# RC_module.net
KiCad netlist of a schematic drawn in EAGLE
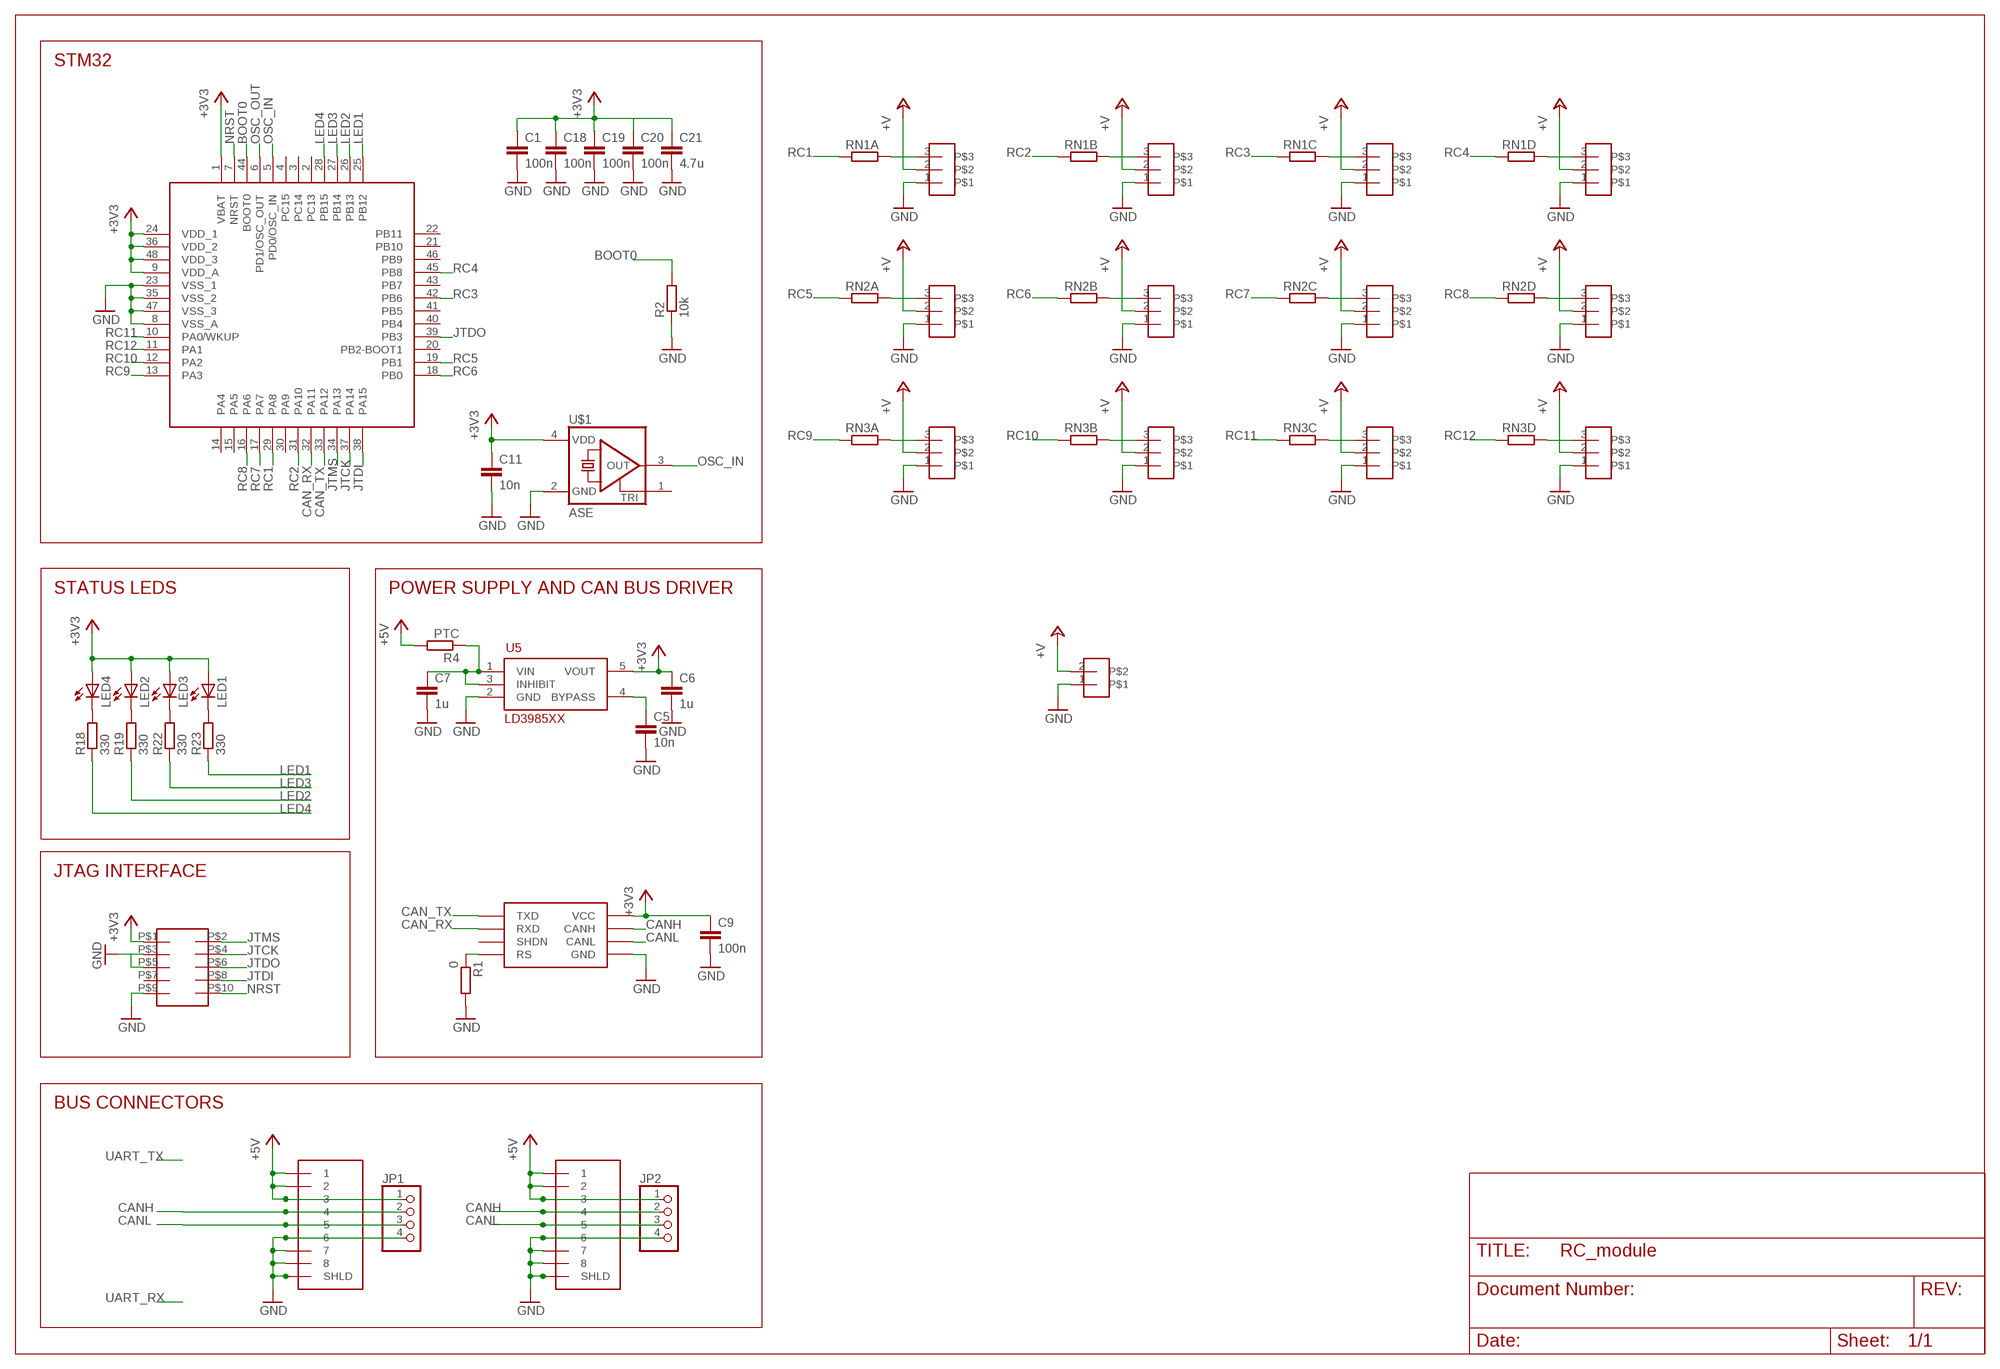
[diagram p0: schematic, sheet 1]

(export (version "E")
  (design (tool "Eeschema 10.0.6"))
  (components
    (comp (ref "1")
      (value "RJ45-43860")
      (footprint "eagle-import:0438600010")
      (libsource (lib "eagle-import") (part "RJ45-43860"))
    )
    (comp (ref "2")
      (value "RJ45-43860")
      (footprint "eagle-import:0438600010")
      (libsource (lib "eagle-import") (part "RJ45-43860"))
    )
    (comp (ref "C1")
      (value "100n")
      (footprint "eagle-import:C0603")
      (libsource (lib "eagle-import") (part "C-EUC0603"))
    )
    (comp (ref "C5")
      (value "10n")
      (footprint "eagle-import:C0603")
      (libsource (lib "eagle-import") (part "C-EUC0603"))
    )
    (comp (ref "C6")
      (value "1u")
      (footprint "eagle-import:C0603")
      (libsource (lib "eagle-import") (part "C-EUC0603"))
    )
    (comp (ref "C7")
      (value "1u")
      (footprint "eagle-import:C0603")
      (libsource (lib "eagle-import") (part "C-EUC0603"))
    )
    (comp (ref "C9")
      (value "100n")
      (footprint "eagle-import:C0603")
      (libsource (lib "eagle-import") (part "C-EUC0603"))
    )
    (comp (ref "C11")
      (value "10n")
      (footprint "eagle-import:C0603")
      (libsource (lib "eagle-import") (part "C-EUC0603"))
    )
    (comp (ref "C18")
      (value "100n")
      (footprint "eagle-import:C0603")
      (libsource (lib "eagle-import") (part "C-EUC0603"))
    )
    (comp (ref "C19")
      (value "100n")
      (footprint "eagle-import:C0603")
      (libsource (lib "eagle-import") (part "C-EUC0603"))
    )
    (comp (ref "C20")
      (value "100n")
      (footprint "eagle-import:C0603")
      (libsource (lib "eagle-import") (part "C-EUC0603"))
    )
    (comp (ref "C21")
      (value "4.7u")
      (footprint "eagle-import:C0805")
      (libsource (lib "eagle-import") (part "C-EUC0805"))
    )
    (comp (ref "JP1")
      (value "PINHD-1X4")
      (footprint "eagle-import:1X04")
      (libsource (lib "eagle-import") (part "PINHD-1X4"))
    )
    (comp (ref "JP2")
      (value "PINHD-1X4")
      (footprint "eagle-import:1X04")
      (libsource (lib "eagle-import") (part "PINHD-1X4"))
    )
    (comp (ref "LED1")
      (value "LEDCHIPLED_0805")
      (footprint "eagle-import:CHIPLED_0805")
      (libsource (lib "eagle-import") (part "LEDCHIPLED_0805"))
    )
    (comp (ref "LED2")
      (value "LEDCHIPLED_0805")
      (footprint "eagle-import:CHIPLED_0805")
      (libsource (lib "eagle-import") (part "LEDCHIPLED_0805"))
    )
    (comp (ref "LED3")
      (value "LEDCHIPLED_0805")
      (footprint "eagle-import:CHIPLED_0805")
      (libsource (lib "eagle-import") (part "LEDCHIPLED_0805"))
    )
    (comp (ref "LED4")
      (value "LEDCHIPLED_0805")
      (footprint "eagle-import:CHIPLED_0805")
      (libsource (lib "eagle-import") (part "LEDCHIPLED_0805"))
    )
    (comp (ref "R1")
      (value "0")
      (footprint "eagle-import:R0603")
      (libsource (lib "eagle-import") (part "R-EU_R0603"))
    )
    (comp (ref "R2")
      (value "10k")
      (footprint "eagle-import:R0603")
      (libsource (lib "eagle-import") (part "R-EU_R0603"))
    )
    (comp (ref "R4")
      (value "PTC")
      (footprint "eagle-import:R0603")
      (libsource (lib "eagle-import") (part "R-EU_R0603"))
    )
    (comp (ref "R18")
      (value "330")
      (footprint "eagle-import:R0603")
      (libsource (lib "eagle-import") (part "R-EU_R0603"))
    )
    (comp (ref "R19")
      (value "330")
      (footprint "eagle-import:R0603")
      (libsource (lib "eagle-import") (part "R-EU_R0603"))
    )
    (comp (ref "R22")
      (value "330")
      (footprint "eagle-import:R0603")
      (libsource (lib "eagle-import") (part "R-EU_R0603"))
    )
    (comp (ref "R23")
      (value "330")
      (footprint "eagle-import:R0603")
      (libsource (lib "eagle-import") (part "R-EU_R0603"))
    )
    (comp (ref "RN1")
      (value "RESISTOR_ARRAY_4")
      (footprint "eagle-import:RN8P-4R-CRA06S")
      (libsource (lib "eagle-import") (part "RESISTOR_ARRAY_4"))
    )
    (comp (ref "RN2")
      (value "RESISTOR_ARRAY_4")
      (footprint "eagle-import:RN8P-4R-CRA06S")
      (libsource (lib "eagle-import") (part "RESISTOR_ARRAY_4"))
    )
    (comp (ref "RN3")
      (value "RESISTOR_ARRAY_4")
      (footprint "eagle-import:RN8P-4R-CRA06S")
      (libsource (lib "eagle-import") (part "RESISTOR_ARRAY_4"))
    )
    (comp (ref "SOT1")
      (value "MAX3051")
      (footprint "eagle-import:SOT23-8L")
      (libsource (lib "eagle-import") (part "MAX3051"))
    )
    (comp (ref "U$1")
      (value "ASE")
      (footprint "eagle-import:ASE")
      (libsource (lib "eagle-import") (part "ASE"))
    )
    (comp (ref "U$2")
      (value "PINHD-3")
      (footprint "eagle-import:1X03")
      (libsource (lib "eagle-import") (part "PINHD-3"))
    )
    (comp (ref "U$3")
      (value "PINHD-3")
      (footprint "eagle-import:1X03")
      (libsource (lib "eagle-import") (part "PINHD-3"))
    )
    (comp (ref "U$4")
      (value "FTSH-105")
      (footprint "eagle-import:FTSH-105")
      (libsource (lib "eagle-import") (part "FTSH-105"))
    )
    (comp (ref "U$5")
      (value "PINHD-3")
      (footprint "eagle-import:1X03")
      (libsource (lib "eagle-import") (part "PINHD-3"))
    )
    (comp (ref "U$6")
      (value "PINHD-3")
      (footprint "eagle-import:1X03")
      (libsource (lib "eagle-import") (part "PINHD-3"))
    )
    (comp (ref "U$7")
      (value "PINHD-3")
      (footprint "eagle-import:1X03")
      (libsource (lib "eagle-import") (part "PINHD-3"))
    )
    (comp (ref "U$8")
      (value "PINHD-3")
      (footprint "eagle-import:1X03")
      (libsource (lib "eagle-import") (part "PINHD-3"))
    )
    (comp (ref "U$9")
      (value "PINHD-3")
      (footprint "eagle-import:1X03")
      (libsource (lib "eagle-import") (part "PINHD-3"))
    )
    (comp (ref "U$10")
      (value "PINHD-3")
      (footprint "eagle-import:1X03")
      (libsource (lib "eagle-import") (part "PINHD-3"))
    )
    (comp (ref "U$11")
      (value "PINHD-3")
      (footprint "eagle-import:1X03")
      (libsource (lib "eagle-import") (part "PINHD-3"))
    )
    (comp (ref "U$12")
      (value "PINHD-3")
      (footprint "eagle-import:1X03")
      (libsource (lib "eagle-import") (part "PINHD-3"))
    )
    (comp (ref "U$13")
      (value "PINHD-3")
      (footprint "eagle-import:1X03")
      (libsource (lib "eagle-import") (part "PINHD-3"))
    )
    (comp (ref "U$14")
      (value "PINHD-3")
      (footprint "eagle-import:1X03")
      (libsource (lib "eagle-import") (part "PINHD-3"))
    )
    (comp (ref "U$15")
      (value "SCREWTERMINAL_3-3")
      (footprint "eagle-import:SCREWTERMINAL-3.5MM-2")
      (libsource (lib "eagle-import") (part "SCREWTERMINAL_3-3"))
    )
    (comp (ref "U1")
      (value "STM32F103CX")
      (footprint "eagle-import:LQFP48")
      (libsource (lib "eagle-import") (part "STM32F103CX"))
    )
    (comp (ref "U5")
      (value "LD3985XX")
      (footprint "eagle-import:SOT23-5L")
      (libsource (lib "eagle-import") (part "LD3985XX"))
    )
  )
  (nets
    (net (code "1") (name "+3V3") (class "Default")
      (node (ref "C1") (pin "1") (pinfunction "1_1") (pintype "passive"))
      (node (ref "C11") (pin "1") (pinfunction "1_1") (pintype "passive"))
      (node (ref "C18") (pin "1") (pinfunction "1_1") (pintype "passive"))
      (node (ref "C19") (pin "1") (pinfunction "1_1") (pintype "passive"))
      (node (ref "C20") (pin "1") (pinfunction "1_1") (pintype "passive"))
      (node (ref "C21") (pin "1") (pinfunction "1_1") (pintype "passive"))
      (node (ref "C6") (pin "1") (pinfunction "1_1") (pintype "passive"))
      (node (ref "C9") (pin "1") (pinfunction "1_1") (pintype "passive"))
      (node (ref "LED1") (pin "A") (pinfunction "A_A") (pintype "passive"))
      (node (ref "LED2") (pin "A") (pinfunction "A_A") (pintype "passive"))
      (node (ref "LED3") (pin "A") (pinfunction "A_A") (pintype "passive"))
      (node (ref "LED4") (pin "A") (pinfunction "A_A") (pintype "passive"))
      (node (ref "SOT1") (pin "P$3") (pinfunction "VCC_P$3") (pintype "bidirectional"))
      (node (ref "U$1") (pin "4") (pinfunction "VDD_4") (pintype "power_in"))
      (node (ref "U$4") (pin "P$1") (pinfunction "P$1_P$1") (pintype "bidirectional"))
      (node (ref "U1") (pin "1") (pinfunction "VBAT_1") (pintype "bidirectional"))
      (node (ref "U1") (pin "24") (pinfunction "VDD_1_24") (pintype "bidirectional"))
      (node (ref "U1") (pin "36") (pinfunction "VDD_2_36") (pintype "bidirectional"))
      (node (ref "U1") (pin "48") (pinfunction "VDD_3_48") (pintype "bidirectional"))
      (node (ref "U1") (pin "9") (pinfunction "VDD_A_9") (pintype "bidirectional"))
      (node (ref "U5") (pin "5") (pinfunction "VOUT_5") (pintype "bidirectional"))
    )
    (net (code "2") (name "+5V") (class "Default")
      (node (ref "1") (pin "P$1") (pinfunction "1_P$1") (pintype "bidirectional"))
      (node (ref "1") (pin "P$2") (pinfunction "2_P$2") (pintype "bidirectional"))
      (node (ref "1") (pin "P$3") (pinfunction "3_P$3") (pintype "bidirectional"))
      (node (ref "2") (pin "P$1") (pinfunction "1_P$1") (pintype "bidirectional"))
      (node (ref "2") (pin "P$2") (pinfunction "2_P$2") (pintype "bidirectional"))
      (node (ref "2") (pin "P$3") (pinfunction "3_P$3") (pintype "bidirectional"))
      (node (ref "JP1") (pin "1") (pinfunction "1_1") (pintype "passive"))
      (node (ref "JP2") (pin "1") (pinfunction "1_1") (pintype "passive"))
      (node (ref "R4") (pin "2") (pinfunction "2_2") (pintype "passive"))
    )
    (net (code "3") (name "+V") (class "Default")
      (node (ref "U$10") (pin "2") (pinfunction "P$2_2") (pintype "bidirectional"))
      (node (ref "U$11") (pin "2") (pinfunction "P$2_2") (pintype "bidirectional"))
      (node (ref "U$12") (pin "2") (pinfunction "P$2_2") (pintype "bidirectional"))
      (node (ref "U$13") (pin "2") (pinfunction "P$2_2") (pintype "bidirectional"))
      (node (ref "U$14") (pin "2") (pinfunction "P$2_2") (pintype "bidirectional"))
      (node (ref "U$15") (pin "2") (pinfunction "P$2_2") (pintype "bidirectional"))
      (node (ref "U$2") (pin "2") (pinfunction "P$2_2") (pintype "bidirectional"))
      (node (ref "U$3") (pin "2") (pinfunction "P$2_2") (pintype "bidirectional"))
      (node (ref "U$5") (pin "2") (pinfunction "P$2_2") (pintype "bidirectional"))
      (node (ref "U$6") (pin "2") (pinfunction "P$2_2") (pintype "bidirectional"))
      (node (ref "U$7") (pin "2") (pinfunction "P$2_2") (pintype "bidirectional"))
      (node (ref "U$8") (pin "2") (pinfunction "P$2_2") (pintype "bidirectional"))
      (node (ref "U$9") (pin "2") (pinfunction "P$2_2") (pintype "bidirectional"))
    )
    (net (code "4") (name "/BOOT0") (class "Default")
      (node (ref "R2") (pin "2") (pinfunction "2_2") (pintype "passive"))
      (node (ref "U1") (pin "44") (pinfunction "BOOT0_44") (pintype "bidirectional"))
    )
    (net (code "5") (name "/CANH") (class "Default")
      (node (ref "1") (pin "P$4") (pinfunction "4_P$4") (pintype "bidirectional"))
      (node (ref "2") (pin "P$4") (pinfunction "4_P$4") (pintype "bidirectional"))
      (node (ref "JP1") (pin "2") (pinfunction "2_2") (pintype "passive"))
      (node (ref "JP2") (pin "2") (pinfunction "2_2") (pintype "passive"))
      (node (ref "SOT1") (pin "P$7") (pinfunction "CANH_P$7") (pintype "bidirectional"))
    )
    (net (code "6") (name "/CANL") (class "Default")
      (node (ref "1") (pin "P$5") (pinfunction "5_P$5") (pintype "bidirectional"))
      (node (ref "2") (pin "P$5") (pinfunction "5_P$5") (pintype "bidirectional"))
      (node (ref "JP1") (pin "3") (pinfunction "3_3") (pintype "passive"))
      (node (ref "JP2") (pin "3") (pinfunction "3_3") (pintype "passive"))
      (node (ref "SOT1") (pin "P$6") (pinfunction "CANL_P$6") (pintype "bidirectional"))
    )
    (net (code "7") (name "/CAN_RX") (class "Default")
      (node (ref "SOT1") (pin "P$4") (pinfunction "RXD_P$4") (pintype "bidirectional"))
      (node (ref "U1") (pin "32") (pinfunction "PA11_32") (pintype "bidirectional"))
    )
    (net (code "8") (name "/CAN_TX") (class "Default")
      (node (ref "SOT1") (pin "P$1") (pinfunction "TXD_P$1") (pintype "bidirectional"))
      (node (ref "U1") (pin "33") (pinfunction "PA12_33") (pintype "bidirectional"))
    )
    (net (code "9") (name "/JTCK") (class "Default")
      (node (ref "U$4") (pin "P$4") (pinfunction "P$4_P$4") (pintype "bidirectional"))
      (node (ref "U1") (pin "37") (pinfunction "PA14_37") (pintype "bidirectional"))
    )
    (net (code "10") (name "/JTDI") (class "Default")
      (node (ref "U$4") (pin "P$8") (pinfunction "P$8_P$8") (pintype "bidirectional"))
      (node (ref "U1") (pin "38") (pinfunction "PA15_38") (pintype "bidirectional"))
    )
    (net (code "11") (name "/JTDO") (class "Default")
      (node (ref "U$4") (pin "P$6") (pinfunction "P$6_P$6") (pintype "bidirectional"))
      (node (ref "U1") (pin "39") (pinfunction "PB3_39") (pintype "bidirectional"))
    )
    (net (code "12") (name "/JTMS") (class "Default")
      (node (ref "U$4") (pin "P$2") (pinfunction "P$2_P$2") (pintype "bidirectional"))
      (node (ref "U1") (pin "34") (pinfunction "PA13_34") (pintype "bidirectional"))
    )
    (net (code "13") (name "/LED1") (class "Default")
      (node (ref "R23") (pin "1") (pinfunction "1_1") (pintype "passive"))
      (node (ref "U1") (pin "25") (pinfunction "PB12_25") (pintype "bidirectional"))
    )
    (net (code "14") (name "/LED2") (class "Default")
      (node (ref "R19") (pin "1") (pinfunction "1_1") (pintype "passive"))
      (node (ref "U1") (pin "26") (pinfunction "PB13_26") (pintype "bidirectional"))
    )
    (net (code "15") (name "/LED3") (class "Default")
      (node (ref "R22") (pin "1") (pinfunction "1_1") (pintype "passive"))
      (node (ref "U1") (pin "27") (pinfunction "PB14_27") (pintype "bidirectional"))
    )
    (net (code "16") (name "/LED4") (class "Default")
      (node (ref "R18") (pin "1") (pinfunction "1_1") (pintype "passive"))
      (node (ref "U1") (pin "28") (pinfunction "PB15_28") (pintype "bidirectional"))
    )
    (net (code "17") (name "/NRST") (class "Default")
      (node (ref "U$4") (pin "P$10") (pinfunction "P$10_P$10") (pintype "bidirectional"))
      (node (ref "U1") (pin "7") (pinfunction "NRST_7") (pintype "bidirectional"))
    )
    (net (code "18") (name "/OSC_IN") (class "Default")
      (node (ref "U$1") (pin "3") (pinfunction "OUT_3") (pintype "output"))
      (node (ref "U1") (pin "5") (pinfunction "PD0/OSC_IN_5") (pintype "bidirectional"))
    )
    (net (code "19") (name "/OSC_OUT") (class "Default")
      (node (ref "U1") (pin "6") (pinfunction "PD1/OSC_OUT_6") (pintype "bidirectional"))
    )
    (net (code "20") (name "/RC1") (class "Default")
      (node (ref "RN1") (pin "1") (pinfunction "1_1") (pintype "passive"))
      (node (ref "U1") (pin "29") (pinfunction "PA8_29") (pintype "bidirectional"))
    )
    (net (code "21") (name "/RC2") (class "Default")
      (node (ref "RN1") (pin "2") (pinfunction "1_2") (pintype "passive"))
      (node (ref "U1") (pin "31") (pinfunction "PA10_31") (pintype "bidirectional"))
    )
    (net (code "22") (name "/RC3") (class "Default")
      (node (ref "RN1") (pin "3") (pinfunction "1_3") (pintype "passive"))
      (node (ref "U1") (pin "42") (pinfunction "PB6_42") (pintype "bidirectional"))
    )
    (net (code "23") (name "/RC4") (class "Default")
      (node (ref "RN1") (pin "4") (pinfunction "1_4") (pintype "passive"))
      (node (ref "U1") (pin "45") (pinfunction "PB8_45") (pintype "bidirectional"))
    )
    (net (code "24") (name "/RC5") (class "Default")
      (node (ref "RN2") (pin "1") (pinfunction "1_1") (pintype "passive"))
      (node (ref "U1") (pin "19") (pinfunction "PB1_19") (pintype "bidirectional"))
    )
    (net (code "25") (name "/RC6") (class "Default")
      (node (ref "RN2") (pin "2") (pinfunction "1_2") (pintype "passive"))
      (node (ref "U1") (pin "18") (pinfunction "PB0_18") (pintype "bidirectional"))
    )
    (net (code "26") (name "/RC7") (class "Default")
      (node (ref "RN2") (pin "3") (pinfunction "1_3") (pintype "passive"))
      (node (ref "U1") (pin "17") (pinfunction "PA7_17") (pintype "bidirectional"))
    )
    (net (code "27") (name "/RC8") (class "Default")
      (node (ref "RN2") (pin "4") (pinfunction "1_4") (pintype "passive"))
      (node (ref "U1") (pin "16") (pinfunction "PA6_16") (pintype "bidirectional"))
    )
    (net (code "28") (name "/RC9") (class "Default")
      (node (ref "RN3") (pin "1") (pinfunction "1_1") (pintype "passive"))
      (node (ref "U1") (pin "13") (pinfunction "PA3_13") (pintype "bidirectional"))
    )
    (net (code "29") (name "/RC10") (class "Default")
      (node (ref "RN3") (pin "2") (pinfunction "1_2") (pintype "passive"))
      (node (ref "U1") (pin "12") (pinfunction "PA2_12") (pintype "bidirectional"))
    )
    (net (code "30") (name "/RC11") (class "Default")
      (node (ref "RN3") (pin "3") (pinfunction "1_3") (pintype "passive"))
      (node (ref "U1") (pin "10") (pinfunction "PA0/WKUP_10") (pintype "bidirectional"))
    )
    (net (code "31") (name "/RC12") (class "Default")
      (node (ref "RN3") (pin "4") (pinfunction "1_4") (pintype "passive"))
      (node (ref "U1") (pin "11") (pinfunction "PA1_11") (pintype "bidirectional"))
    )
    (net (code "34") (name "GND") (class "Default")
      (node (ref "1") (pin "P$10") (pinfunction "P$1_P$10") (pintype "power_in"))
      (node (ref "1") (pin "P$6") (pinfunction "6_P$6") (pintype "bidirectional"))
      (node (ref "1") (pin "P$7") (pinfunction "7_P$7") (pintype "bidirectional"))
      (node (ref "1") (pin "P$8") (pinfunction "8_P$8") (pintype "bidirectional"))
      (node (ref "1") (pin "P$9") (pinfunction "SHLD_P$9") (pintype "power_in"))
      (node (ref "2") (pin "P$10") (pinfunction "P$1_P$10") (pintype "power_in"))
      (node (ref "2") (pin "P$6") (pinfunction "6_P$6") (pintype "bidirectional"))
      (node (ref "2") (pin "P$7") (pinfunction "7_P$7") (pintype "bidirectional"))
      (node (ref "2") (pin "P$8") (pinfunction "8_P$8") (pintype "bidirectional"))
      (node (ref "2") (pin "P$9") (pinfunction "SHLD_P$9") (pintype "power_in"))
      (node (ref "C1") (pin "2") (pinfunction "2_2") (pintype "passive"))
      (node (ref "C11") (pin "2") (pinfunction "2_2") (pintype "passive"))
      (node (ref "C18") (pin "2") (pinfunction "2_2") (pintype "passive"))
      (node (ref "C19") (pin "2") (pinfunction "2_2") (pintype "passive"))
      (node (ref "C20") (pin "2") (pinfunction "2_2") (pintype "passive"))
      (node (ref "C21") (pin "2") (pinfunction "2_2") (pintype "passive"))
      (node (ref "C5") (pin "2") (pinfunction "2_2") (pintype "passive"))
      (node (ref "C6") (pin "2") (pinfunction "2_2") (pintype "passive"))
      (node (ref "C7") (pin "2") (pinfunction "2_2") (pintype "passive"))
      (node (ref "C9") (pin "2") (pinfunction "2_2") (pintype "passive"))
      (node (ref "JP1") (pin "4") (pinfunction "4_4") (pintype "passive"))
      (node (ref "JP2") (pin "4") (pinfunction "4_4") (pintype "passive"))
      (node (ref "R1") (pin "2") (pinfunction "2_2") (pintype "passive"))
      (node (ref "R2") (pin "1") (pinfunction "1_1") (pintype "passive"))
      (node (ref "SOT1") (pin "P$2") (pinfunction "GND_P$2") (pintype "bidirectional"))
      (node (ref "U$1") (pin "2") (pinfunction "GND_2") (pintype "power_in"))
      (node (ref "U$10") (pin "1") (pinfunction "P$1_1") (pintype "bidirectional"))
      (node (ref "U$11") (pin "1") (pinfunction "P$1_1") (pintype "bidirectional"))
      (node (ref "U$12") (pin "1") (pinfunction "P$1_1") (pintype "bidirectional"))
      (node (ref "U$13") (pin "1") (pinfunction "P$1_1") (pintype "bidirectional"))
      (node (ref "U$14") (pin "1") (pinfunction "P$1_1") (pintype "bidirectional"))
      (node (ref "U$15") (pin "1") (pinfunction "P$1_1") (pintype "bidirectional"))
      (node (ref "U$2") (pin "1") (pinfunction "P$1_1") (pintype "bidirectional"))
      (node (ref "U$3") (pin "1") (pinfunction "P$1_1") (pintype "bidirectional"))
      (node (ref "U$4") (pin "P$3") (pinfunction "P$3_P$3") (pintype "bidirectional"))
      (node (ref "U$4") (pin "P$9") (pinfunction "P$9_P$9") (pintype "bidirectional"))
      (node (ref "U$5") (pin "1") (pinfunction "P$1_1") (pintype "bidirectional"))
      (node (ref "U$6") (pin "1") (pinfunction "P$1_1") (pintype "bidirectional"))
      (node (ref "U$7") (pin "1") (pinfunction "P$1_1") (pintype "bidirectional"))
      (node (ref "U$8") (pin "1") (pinfunction "P$1_1") (pintype "bidirectional"))
      (node (ref "U$9") (pin "1") (pinfunction "P$1_1") (pintype "bidirectional"))
      (node (ref "U1") (pin "23") (pinfunction "VSS_1_23") (pintype "bidirectional"))
      (node (ref "U1") (pin "35") (pinfunction "VSS_2_35") (pintype "bidirectional"))
      (node (ref "U1") (pin "47") (pinfunction "VSS_3_47") (pintype "bidirectional"))
      (node (ref "U1") (pin "8") (pinfunction "VSS_A_8") (pintype "bidirectional"))
      (node (ref "U5") (pin "2") (pinfunction "GND_2") (pintype "bidirectional"))
    )
    (net (code "35") (name "Net-(LED1-PadC)") (class "Default")
      (node (ref "LED1") (pin "C") (pinfunction "C_C") (pintype "passive"))
      (node (ref "R23") (pin "2") (pinfunction "2_2") (pintype "passive"))
    )
    (net (code "36") (name "Net-(LED2-PadC)") (class "Default")
      (node (ref "LED2") (pin "C") (pinfunction "C_C") (pintype "passive"))
      (node (ref "R19") (pin "2") (pinfunction "2_2") (pintype "passive"))
    )
    (net (code "37") (name "Net-(LED3-PadC)") (class "Default")
      (node (ref "LED3") (pin "C") (pinfunction "C_C") (pintype "passive"))
      (node (ref "R22") (pin "2") (pinfunction "2_2") (pintype "passive"))
    )
    (net (code "38") (name "Net-(LED4-PadC)") (class "Default")
      (node (ref "LED4") (pin "C") (pinfunction "C_C") (pintype "passive"))
      (node (ref "R18") (pin "2") (pinfunction "2_2") (pintype "passive"))
    )
    (net (code "39") (name "Net-(RN1A-2)") (class "Default")
      (node (ref "RN1") (pin "8") (pinfunction "2_8") (pintype "passive"))
      (node (ref "U$2") (pin "3") (pinfunction "P$3_3") (pintype "bidirectional"))
    )
    (net (code "40") (name "Net-(RN1B-2)") (class "Default")
      (node (ref "RN1") (pin "7") (pinfunction "2_7") (pintype "passive"))
      (node (ref "U$3") (pin "3") (pinfunction "P$3_3") (pintype "bidirectional"))
    )
    (net (code "41") (name "Net-(RN1C-2)") (class "Default")
      (node (ref "RN1") (pin "6") (pinfunction "2_6") (pintype "passive"))
      (node (ref "U$5") (pin "3") (pinfunction "P$3_3") (pintype "bidirectional"))
    )
    (net (code "42") (name "Net-(RN1D-2)") (class "Default")
      (node (ref "RN1") (pin "5") (pinfunction "2_5") (pintype "passive"))
      (node (ref "U$6") (pin "3") (pinfunction "P$3_3") (pintype "bidirectional"))
    )
    (net (code "43") (name "Net-(RN2A-2)") (class "Default")
      (node (ref "RN2") (pin "8") (pinfunction "2_8") (pintype "passive"))
      (node (ref "U$7") (pin "3") (pinfunction "P$3_3") (pintype "bidirectional"))
    )
    (net (code "44") (name "Net-(RN2B-2)") (class "Default")
      (node (ref "RN2") (pin "7") (pinfunction "2_7") (pintype "passive"))
      (node (ref "U$8") (pin "3") (pinfunction "P$3_3") (pintype "bidirectional"))
    )
    (net (code "45") (name "Net-(RN2C-2)") (class "Default")
      (node (ref "RN2") (pin "6") (pinfunction "2_6") (pintype "passive"))
      (node (ref "U$9") (pin "3") (pinfunction "P$3_3") (pintype "bidirectional"))
    )
    (net (code "46") (name "Net-(RN2D-2)") (class "Default")
      (node (ref "RN2") (pin "5") (pinfunction "2_5") (pintype "passive"))
      (node (ref "U$10") (pin "3") (pinfunction "P$3_3") (pintype "bidirectional"))
    )
    (net (code "47") (name "Net-(RN3A-2)") (class "Default")
      (node (ref "RN3") (pin "8") (pinfunction "2_8") (pintype "passive"))
      (node (ref "U$11") (pin "3") (pinfunction "P$3_3") (pintype "bidirectional"))
    )
    (net (code "48") (name "Net-(RN3B-2)") (class "Default")
      (node (ref "RN3") (pin "7") (pinfunction "2_7") (pintype "passive"))
      (node (ref "U$12") (pin "3") (pinfunction "P$3_3") (pintype "bidirectional"))
    )
    (net (code "49") (name "Net-(RN3C-2)") (class "Default")
      (node (ref "RN3") (pin "6") (pinfunction "2_6") (pintype "passive"))
      (node (ref "U$13") (pin "3") (pinfunction "P$3_3") (pintype "bidirectional"))
    )
    (net (code "50") (name "Net-(RN3D-2)") (class "Default")
      (node (ref "RN3") (pin "5") (pinfunction "2_5") (pintype "passive"))
      (node (ref "U$14") (pin "3") (pinfunction "P$3_3") (pintype "bidirectional"))
    )
    (net (code "51") (name "Net-(SOT1-RS)") (class "Default")
      (node (ref "R1") (pin "1") (pinfunction "1_1") (pintype "passive"))
      (node (ref "SOT1") (pin "P$8") (pinfunction "RS_P$8") (pintype "bidirectional"))
    )
    (net (code "52") (name "Net-(U5-BYPASS)") (class "Default")
      (node (ref "C5") (pin "1") (pinfunction "1_1") (pintype "passive"))
      (node (ref "U5") (pin "4") (pinfunction "BYPASS_4") (pintype "bidirectional"))
    )
    (net (code "53") (name "Net-(U5-INHIBIT)") (class "Default")
      (node (ref "C7") (pin "1") (pinfunction "1_1") (pintype "passive"))
      (node (ref "R4") (pin "1") (pinfunction "1_1") (pintype "passive"))
      (node (ref "U5") (pin "1") (pinfunction "VIN_1") (pintype "bidirectional"))
      (node (ref "U5") (pin "3") (pinfunction "INHIBIT_3") (pintype "bidirectional"))
    )
    (net (code "54") (name "unconnected-(SOT1-SHDN-PadP$5)") (class "Default")
      (node (ref "SOT1") (pin "P$5") (pinfunction "SHDN_P$5") (pintype "bidirectional"))
    )
    (net (code "55") (name "unconnected-(U$1-TRI-Pad1)") (class "Default")
      (node (ref "U$1") (pin "1") (pinfunction "TRI_1") (pintype "input"))
    )
    (net (code "56") (name "unconnected-(U$4-PadP$5)") (class "Default")
      (node (ref "U$4") (pin "P$5") (pinfunction "P$5_P$5") (pintype "bidirectional"))
    )
    (net (code "57") (name "unconnected-(U$4-PadP$7)") (class "Default")
      (node (ref "U$4") (pin "P$7") (pinfunction "P$7_P$7") (pintype "bidirectional"))
    )
    (net (code "58") (name "unconnected-(U1-PA4-Pad14)") (class "Default")
      (node (ref "U1") (pin "14") (pinfunction "PA4_14") (pintype "bidirectional"))
    )
    (net (code "59") (name "unconnected-(U1-PA5-Pad15)") (class "Default")
      (node (ref "U1") (pin "15") (pinfunction "PA5_15") (pintype "bidirectional"))
    )
    (net (code "60") (name "unconnected-(U1-PA9-Pad30)") (class "Default")
      (node (ref "U1") (pin "30") (pinfunction "PA9_30") (pintype "bidirectional"))
    )
    (net (code "61") (name "unconnected-(U1-PB2-BOOT1-Pad20)") (class "Default")
      (node (ref "U1") (pin "20") (pinfunction "PB2-BOOT1_20") (pintype "bidirectional"))
    )
    (net (code "62") (name "unconnected-(U1-PB4-Pad40)") (class "Default")
      (node (ref "U1") (pin "40") (pinfunction "PB4_40") (pintype "bidirectional"))
    )
    (net (code "63") (name "unconnected-(U1-PB5-Pad41)") (class "Default")
      (node (ref "U1") (pin "41") (pinfunction "PB5_41") (pintype "bidirectional"))
    )
    (net (code "64") (name "unconnected-(U1-PB7-Pad43)") (class "Default")
      (node (ref "U1") (pin "43") (pinfunction "PB7_43") (pintype "bidirectional"))
    )
    (net (code "65") (name "unconnected-(U1-PB9-Pad46)") (class "Default")
      (node (ref "U1") (pin "46") (pinfunction "PB9_46") (pintype "bidirectional"))
    )
    (net (code "66") (name "unconnected-(U1-PB10-Pad21)") (class "Default")
      (node (ref "U1") (pin "21") (pinfunction "PB10_21") (pintype "bidirectional"))
    )
    (net (code "67") (name "unconnected-(U1-PB11-Pad22)") (class "Default")
      (node (ref "U1") (pin "22") (pinfunction "PB11_22") (pintype "bidirectional"))
    )
    (net (code "68") (name "unconnected-(U1-PC13-Pad2)") (class "Default")
      (node (ref "U1") (pin "2") (pinfunction "PC13_2") (pintype "bidirectional"))
    )
    (net (code "69") (name "unconnected-(U1-PC14-Pad3)") (class "Default")
      (node (ref "U1") (pin "3") (pinfunction "PC14_3") (pintype "bidirectional"))
    )
    (net (code "70") (name "unconnected-(U1-PC15-Pad4)") (class "Default")
      (node (ref "U1") (pin "4") (pinfunction "PC15_4") (pintype "bidirectional"))
    )
  )
)
